# Standing_Desk_Controller_Schematic_v7_v9.net
KiCad netlist of a schematic drawn in EAGLE
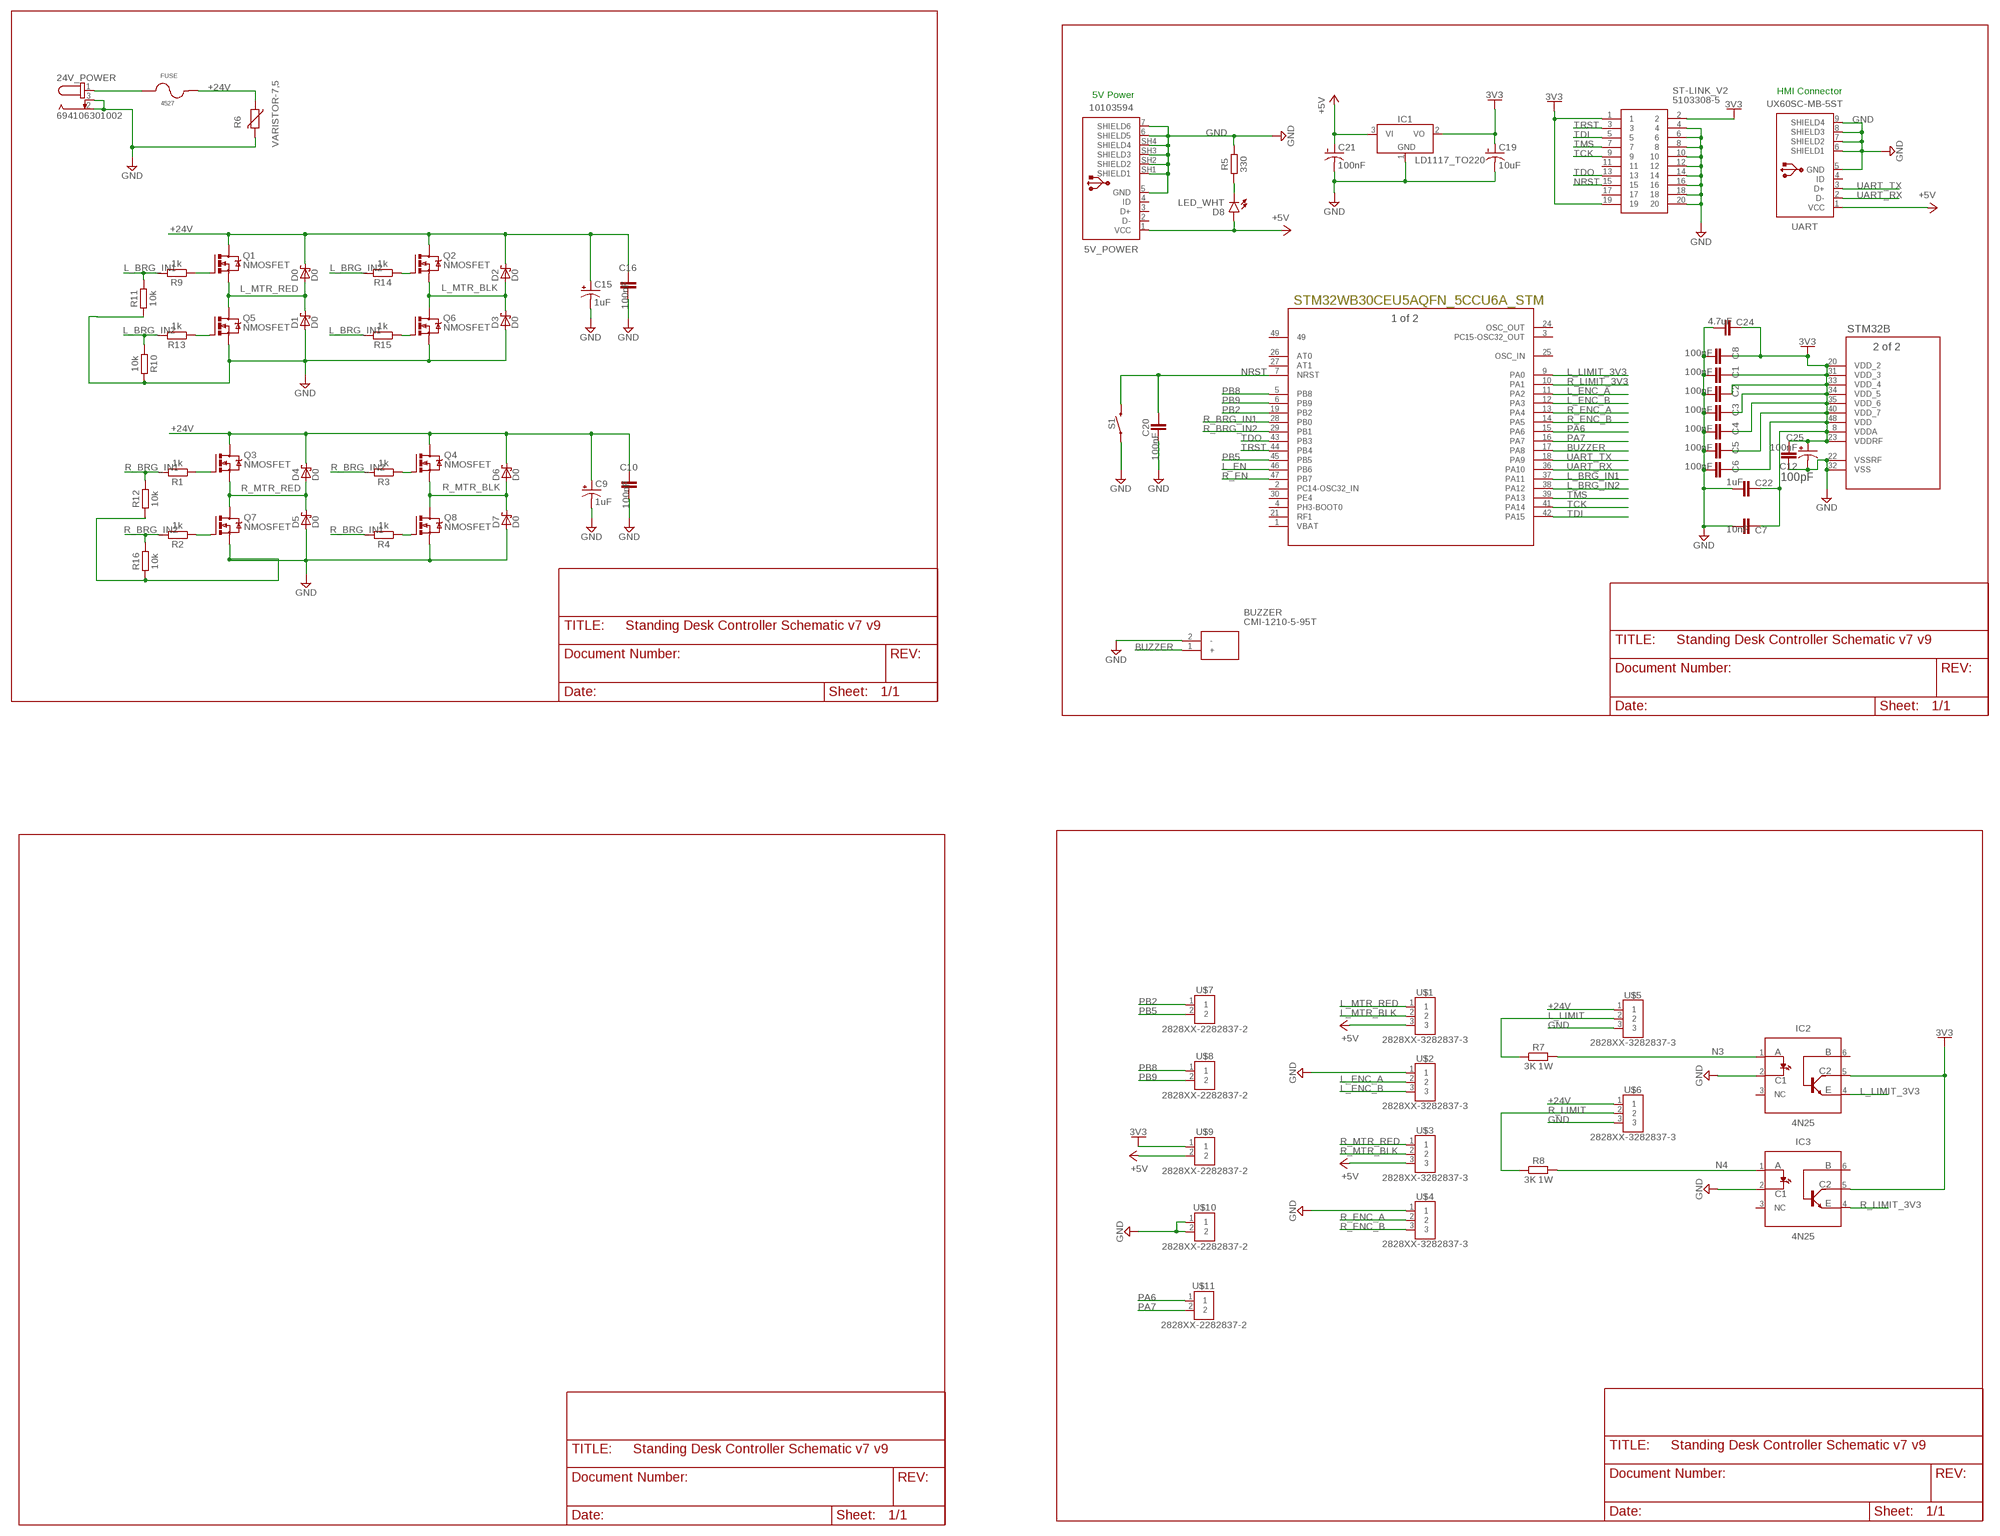
[diagram p0: schematic, sheet 1]

(export (version "E")
  (design (tool "Eeschema 10.0.6"))
  (components
    (comp (ref "5V_POWER")
      (value "10103594")
      (footprint "eagle-import:10103594")
      (fields (field (name "MANUFACTURER") "Amphenol ICC (FCI)") (field (name "MPN") "10103594-0001LF"))
      (libsource (lib "eagle-import") (part "10103594"))
    )
    (comp (ref "24V_POWER")
      (value "694106301002")
      (footprint "eagle-import:694106301002")
      (fields
        (field (name "DIGIKEY_PART_NUMBER") "732-5930-ND")
        (field (name "MANUFACTURER") "Wurth Electronics Inc.")
        (field (name "CREATED_BY") "PCBLayout.com")
      )
      (libsource (lib "eagle-import") (part "694106301002"))
    )
    (comp (ref "BUZZER")
      (value "CMI-1210-5-95T")
      (footprint "eagle-import:CMI1210595T")
      (fields (field (name "MOUSER_PART_NUMBER") "179-CMI-1210-5-95T"))
      (libsource (lib "eagle-import") (part "CMI-1210-5-95T"))
    )
    (comp (ref "C1")
      (value "100nF")
      (footprint "eagle-import:CAPC3216X135")
      (libsource (lib "eagle-import") (part "Capacitor_Bottom_Side_vf.a7xvLcyfRC6FgNyyCREhQg_CCHIP-1206(3216-METRIC)_"))
    )
    (comp (ref "C2")
      (value "100nF")
      (footprint "eagle-import:CAPC3216X135")
      (libsource (lib "eagle-import") (part "Capacitor_Bottom_Side_vf.a7xvLcyfRC6FgNyyCREhQg_CCHIP-1206(3216-METRIC)_"))
    )
    (comp (ref "C3")
      (value "100nF")
      (footprint "eagle-import:CAPC3216X135")
      (libsource (lib "eagle-import") (part "Capacitor_Bottom_Side_vf.a7xvLcyfRC6FgNyyCREhQg_CCHIP-1206(3216-METRIC)_"))
    )
    (comp (ref "C4")
      (value "100nF")
      (footprint "eagle-import:CAPC3216X135")
      (libsource (lib "eagle-import") (part "Capacitor_Bottom_Side_vf.a7xvLcyfRC6FgNyyCREhQg_CCHIP-1206(3216-METRIC)_"))
    )
    (comp (ref "C5")
      (value "100nF")
      (footprint "eagle-import:CAPC3216X135")
      (libsource (lib "eagle-import") (part "Capacitor_Bottom_Side_vf.a7xvLcyfRC6FgNyyCREhQg_CCHIP-1206(3216-METRIC)_"))
    )
    (comp (ref "C6")
      (value "100nF")
      (footprint "eagle-import:CAPC3216X135")
      (libsource (lib "eagle-import") (part "Capacitor_Bottom_Side_vf.a7xvLcyfRC6FgNyyCREhQg_CCHIP-1206(3216-METRIC)_"))
    )
    (comp (ref "C7")
      (value "10nF")
      (footprint "eagle-import:CAPRD550W60D1025H1250B")
      (libsource (lib "eagle-import") (part "CRADIAL-12.5MM-DIA_"))
    )
    (comp (ref "C8")
      (value "100nF")
      (footprint "eagle-import:CAPC3216X135")
      (libsource (lib "eagle-import") (part "Capacitor_Bottom_Side_vf.a7xvLcyfRC6FgNyyCREhQg_CCHIP-1206(3216-METRIC)_"))
    )
    (comp (ref "C9")
      (value "1uF")
      (footprint "eagle-import:E2,5-6")
      (libsource (lib "eagle-import") (part "CPOL-USE2.5-6"))
    )
    (comp (ref "C10")
      (value "100nF")
      (footprint "eagle-import:CAPC3216X135")
      (libsource (lib "eagle-import") (part "Capacitor_16290819_CCHIP-1206(3216-METRIC)_"))
    )
    (comp (ref "C12")
      (value "100nF")
      (footprint "eagle-import:CAPC3216X135")
      (libsource (lib "eagle-import") (part "Capacitor_Bottom_Side_vf.a7xvLcyfRC6FgNyyCREhQg_CCHIP-1206(3216-METRIC)_"))
    )
    (comp (ref "C15")
      (value "1uF")
      (footprint "eagle-import:E2,5-6")
      (libsource (lib "eagle-import") (part "CPOL-USE2.5-6"))
    )
    (comp (ref "C16")
      (value "100nF")
      (footprint "eagle-import:CAPC3216X135")
      (libsource (lib "eagle-import") (part "Capacitor_16290819_CCHIP-1206(3216-METRIC)_"))
    )
    (comp (ref "C19")
      (value "10uF")
      (footprint "eagle-import:E2,5-6")
      (libsource (lib "eagle-import") (part "CPOL-USE2.5-6"))
    )
    (comp (ref "C20")
      (value "100nF")
      (footprint "eagle-import:CAPC3216X135")
      (libsource (lib "eagle-import") (part "Capacitor_16290819_CCHIP-1206(3216-METRIC)_"))
    )
    (comp (ref "C21")
      (value "100nF")
      (footprint "eagle-import:E2,5-6")
      (libsource (lib "eagle-import") (part "CPOL-USE2.5-6"))
    )
    (comp (ref "C22")
      (value "1uF")
      (footprint "eagle-import:CAPRD550W60D1025H1250B")
      (libsource (lib "eagle-import") (part "CRADIAL-12.5MM-DIA_"))
    )
    (comp (ref "C24")
      (value "4.7uF")
      (footprint "eagle-import:CAPRD550W60D1025H1250B")
      (libsource (lib "eagle-import") (part "CRADIAL-12.5MM-DIA_"))
    )
    (comp (ref "C25")
      (value "100pF")
      (footprint "eagle-import:E2,5-6")
      (libsource (lib "eagle-import") (part "CPOL-USE2.5-6"))
    )
    (comp (ref "D0")
      (value "D0")
      (footprint "eagle-import:SOD106A-W")
      (libsource (lib "eagle-import") (part "SS14CT-ND"))
    )
    (comp (ref "D1")
      (value "D0")
      (footprint "eagle-import:SOD106A-W")
      (libsource (lib "eagle-import") (part "SS14CT-ND"))
    )
    (comp (ref "D2")
      (value "D0")
      (footprint "eagle-import:SOD106A-W")
      (libsource (lib "eagle-import") (part "SS14CT-ND"))
    )
    (comp (ref "D3")
      (value "D0")
      (footprint "eagle-import:SOD106A-W")
      (libsource (lib "eagle-import") (part "SS14CT-ND"))
    )
    (comp (ref "D4")
      (value "D0")
      (footprint "eagle-import:SOD106A-W")
      (libsource (lib "eagle-import") (part "SS14CT-ND"))
    )
    (comp (ref "D5")
      (value "D0")
      (footprint "eagle-import:SOD106A-W")
      (libsource (lib "eagle-import") (part "SS14CT-ND"))
    )
    (comp (ref "D6")
      (value "D0")
      (footprint "eagle-import:SOD106A-W")
      (libsource (lib "eagle-import") (part "SS14CT-ND"))
    )
    (comp (ref "D7")
      (value "D0")
      (footprint "eagle-import:SOD106A-W")
      (libsource (lib "eagle-import") (part "SS14CT-ND"))
    )
    (comp (ref "D8")
      (value "LED_WHT")
      (footprint "eagle-import:LEDC3216X75N_FLAT-B")
      (libsource (lib "eagle-import") (part "CHIP-FLAT-B_1206"))
    )
    (comp (ref "FUSE")
      (value "4527")
      (footprint "eagle-import:4527")
      (fields
        (field (name "MANUFACTURER") "Keystone Electronics")
        (field (name "CREATED_BY") "PCBLayout.com")
      )
      (libsource (lib "eagle-import") (part "4527"))
    )
    (comp (ref "IC1")
      (value "LD1117_TO220")
      (footprint "eagle-import:TO220V")
      (fields (field (name "MANUFACTURER") "STMicroelectronics") (field (name "MPN") "Generic"))
      (libsource (lib "eagle-import") (part "LD1117_TO220"))
    )
    (comp (ref "IC2")
      (value "4N25")
      (footprint "eagle-import:DIP762W60P254L712H480Q6B")
      (fields (field (name "MANUFACTURER") "Vishay"))
      (libsource (lib "eagle-import") (part "4N25"))
    )
    (comp (ref "IC3")
      (value "4N25")
      (footprint "eagle-import:DIP762W60P254L712H480Q6B")
      (fields (field (name "MANUFACTURER") "Vishay"))
      (libsource (lib "eagle-import") (part "4N25"))
    )
    (comp (ref "Q1")
      (value "NMOSFET")
      (footprint "eagle-import:TO220BV")
      (libsource (lib "eagle-import") (part "NMOSFETTO220_"))
    )
    (comp (ref "Q2")
      (value "NMOSFET")
      (footprint "eagle-import:TO220BV")
      (libsource (lib "eagle-import") (part "NMOSFETTO220_"))
    )
    (comp (ref "Q3")
      (value "NMOSFET")
      (footprint "eagle-import:TO220BV")
      (libsource (lib "eagle-import") (part "NMOSFETTO220_"))
    )
    (comp (ref "Q4")
      (value "NMOSFET")
      (footprint "eagle-import:TO220BV")
      (libsource (lib "eagle-import") (part "NMOSFETTO220_"))
    )
    (comp (ref "Q5")
      (value "NMOSFET")
      (footprint "eagle-import:TO220BV")
      (libsource (lib "eagle-import") (part "NMOSFETTO220_"))
    )
    (comp (ref "Q6")
      (value "NMOSFET")
      (footprint "eagle-import:TO220BV")
      (libsource (lib "eagle-import") (part "NMOSFETTO220_"))
    )
    (comp (ref "Q7")
      (value "NMOSFET")
      (footprint "eagle-import:TO220BV")
      (libsource (lib "eagle-import") (part "NMOSFETTO220_"))
    )
    (comp (ref "Q8")
      (value "NMOSFET")
      (footprint "eagle-import:TO220BV")
      (libsource (lib "eagle-import") (part "NMOSFETTO220_"))
    )
    (comp (ref "R1")
      (value "1k")
      (footprint "eagle-import:RESC3216X70")
      (libsource (lib "eagle-import") (part "RCHIP-1206(3216-METRIC)_"))
    )
    (comp (ref "R2")
      (value "1k")
      (footprint "eagle-import:RESC3216X70")
      (libsource (lib "eagle-import") (part "RCHIP-1206(3216-METRIC)_"))
    )
    (comp (ref "R3")
      (value "1k")
      (footprint "eagle-import:RESC3216X70")
      (libsource (lib "eagle-import") (part "RCHIP-1206(3216-METRIC)_"))
    )
    (comp (ref "R4")
      (value "1k")
      (footprint "eagle-import:RESC3216X70")
      (libsource (lib "eagle-import") (part "RCHIP-1206(3216-METRIC)_"))
    )
    (comp (ref "R5")
      (value "330")
      (footprint "eagle-import:RESC3216X70")
      (libsource (lib "eagle-import") (part "RCHIP-1206(3216-METRIC)_"))
    )
    (comp (ref "R6")
      (value "VARISTOR-7,5")
      (footprint "eagle-import:R-7,5")
      (libsource (lib "eagle-import") (part "VARISTOR-7,5"))
    )
    (comp (ref "R7")
      (value "3K 1W")
      (footprint "eagle-import:RESAD724W46L381D178B")
      (libsource (lib "eagle-import") (part "RAXIAL-7.2MM-PITCH_"))
    )
    (comp (ref "R8")
      (value "3K 1W")
      (footprint "eagle-import:RESAD724W46L381D178B")
      (libsource (lib "eagle-import") (part "RAXIAL-7.2MM-PITCH_"))
    )
    (comp (ref "R9")
      (value "1k")
      (footprint "eagle-import:RESC3216X70")
      (libsource (lib "eagle-import") (part "RCHIP-1206(3216-METRIC)_"))
    )
    (comp (ref "R10")
      (value "10k")
      (footprint "eagle-import:RESC3216X70")
      (libsource (lib "eagle-import") (part "RCHIP-1206(3216-METRIC)_"))
    )
    (comp (ref "R11")
      (value "10k")
      (footprint "eagle-import:RESC3216X70")
      (libsource (lib "eagle-import") (part "RCHIP-1206(3216-METRIC)_"))
    )
    (comp (ref "R12")
      (value "10k")
      (footprint "eagle-import:RESC3216X70")
      (libsource (lib "eagle-import") (part "RCHIP-1206(3216-METRIC)_"))
    )
    (comp (ref "R13")
      (value "1k")
      (footprint "eagle-import:RESC3216X70")
      (libsource (lib "eagle-import") (part "RCHIP-1206(3216-METRIC)_"))
    )
    (comp (ref "R14")
      (value "1k")
      (footprint "eagle-import:RESC3216X70")
      (libsource (lib "eagle-import") (part "RCHIP-1206(3216-METRIC)_"))
    )
    (comp (ref "R15")
      (value "1k")
      (footprint "eagle-import:RESC3216X70")
      (libsource (lib "eagle-import") (part "RCHIP-1206(3216-METRIC)_"))
    )
    (comp (ref "R16")
      (value "10k")
      (footprint "eagle-import:RESC3216X70")
      (libsource (lib "eagle-import") (part "RCHIP-1206(3216-METRIC)_"))
    )
    (comp (ref "S1")
      (value "MOMENTARY-SWITCH-SPST-PTH-6.0MM")
      (footprint "eagle-import:TACTILE_SWITCH_PTH_6.0MM")
      (libsource (lib "eagle-import") (part "MOMENTARY-SWITCH-SPST-PTH-6.0MM"))
    )
    (comp (ref "ST-LINK_V2")
      (value "5103308-5")
      (footprint "eagle-import:SHDR20W66P254_2X10_3289X914X98")
      (fields (field (name "MOUSER_PART_NUMBER") "571-5103308-5"))
      (libsource (lib "eagle-import") (part "5103308-5"))
    )
    (comp (ref "STM32")
      (value "STM32WB30CEU5AQFN_5CCU6A_STM")
      (footprint "eagle-import:QFN_5CCU6A_STM")
      (fields
        (field (name "MANUFACTURER_PART_NUMBER") "STM32WB30CEU5A")
        (field (name "COPYRIGHT") "Copyright (C) 2022 Ultra Librarian. All rights reserved.")
      )
      (libsource (lib "eagle-import") (part "STM32WB30CEU5AQFN_5CCU6A_STM"))
    )
    (comp (ref "U$1")
      (value "2828XX-3282837-3")
      (footprint "eagle-import:TERMBLK_508-3N")
      (fields (field (name "MANUFACTURER") "TE Connectivity") (field (name "MPN") "282837-3"))
      (libsource (lib "eagle-import") (part "2828XX-3282837-3"))
    )
    (comp (ref "U$2")
      (value "2828XX-3282837-3")
      (footprint "eagle-import:TERMBLK_508-3N")
      (fields (field (name "MANUFACTURER") "TE Connectivity") (field (name "MPN") "282837-3"))
      (libsource (lib "eagle-import") (part "2828XX-3282837-3"))
    )
    (comp (ref "U$3")
      (value "2828XX-3282837-3")
      (footprint "eagle-import:TERMBLK_508-3N")
      (fields (field (name "MANUFACTURER") "TE Connectivity") (field (name "MPN") "282837-3"))
      (libsource (lib "eagle-import") (part "2828XX-3282837-3"))
    )
    (comp (ref "U$4")
      (value "2828XX-3282837-3")
      (footprint "eagle-import:TERMBLK_508-3N")
      (fields (field (name "MANUFACTURER") "TE Connectivity") (field (name "MPN") "282837-3"))
      (libsource (lib "eagle-import") (part "2828XX-3282837-3"))
    )
    (comp (ref "U$5")
      (value "2828XX-3282837-3")
      (footprint "eagle-import:TERMBLK_508-3N")
      (fields (field (name "MANUFACTURER") "TE Connectivity") (field (name "MPN") "282837-3"))
      (libsource (lib "eagle-import") (part "2828XX-3282837-3"))
    )
    (comp (ref "U$6")
      (value "2828XX-3282837-3")
      (footprint "eagle-import:TERMBLK_508-3N")
      (fields (field (name "MANUFACTURER") "TE Connectivity") (field (name "MPN") "282837-3"))
      (libsource (lib "eagle-import") (part "2828XX-3282837-3"))
    )
    (comp (ref "U$7")
      (value "2828XX-2282837-2")
      (footprint "eagle-import:TERMBLK_508-2N")
      (fields (field (name "MANUFACTURER") "TE Connectivity") (field (name "MPN") "282837-2"))
      (libsource (lib "eagle-import") (part "2828XX-2282837-2"))
    )
    (comp (ref "U$8")
      (value "2828XX-2282837-2")
      (footprint "eagle-import:TERMBLK_508-2N")
      (fields (field (name "MANUFACTURER") "TE Connectivity") (field (name "MPN") "282837-2"))
      (libsource (lib "eagle-import") (part "2828XX-2282837-2"))
    )
    (comp (ref "U$9")
      (value "2828XX-2282837-2")
      (footprint "eagle-import:TERMBLK_508-2N")
      (fields (field (name "MANUFACTURER") "TE Connectivity") (field (name "MPN") "282837-2"))
      (libsource (lib "eagle-import") (part "2828XX-2282837-2"))
    )
    (comp (ref "U$10")
      (value "2828XX-2282837-2")
      (footprint "eagle-import:TERMBLK_508-2N")
      (fields (field (name "MANUFACTURER") "TE Connectivity") (field (name "MPN") "282837-2"))
      (libsource (lib "eagle-import") (part "2828XX-2282837-2"))
    )
    (comp (ref "U$11")
      (value "2828XX-2282837-2")
      (footprint "eagle-import:TERMBLK_508-2N")
      (fields (field (name "MANUFACTURER") "TE Connectivity") (field (name "MPN") "282837-2"))
      (libsource (lib "eagle-import") (part "2828XX-2282837-2"))
    )
    (comp (ref "UART")
      (value "UX60SC-MB-5ST")
      (footprint "eagle-import:UX60SC-MB-5ST")
      (fields
        (field (name "MANUFACTURER") "Hirose Electric Co. Ltd")
        (field (name "MPN") "UX60SC-MB-5ST(80)")
      )
      (libsource (lib "eagle-import") (part "UX60SC-MB-5ST"))
    )
  )
  (nets
    (net (code "1") (name "+5V") (class "Default")
      (node (ref "5V_POWER") (pin "1") (pinfunction "VCC_1") (pintype "power_in"))
      (node (ref "C21") (pin "+") (pinfunction "+_+") (pintype "passive"))
      (node (ref "D8") (pin "A") (pinfunction "A_A") (pintype "passive"))
      (node (ref "IC1") (pin "3") (pinfunction "VI_3") (pintype "input"))
      (node (ref "U$1") (pin "3") (pinfunction "3_3") (pintype "bidirectional"))
      (node (ref "U$3") (pin "3") (pinfunction "3_3") (pintype "bidirectional"))
      (node (ref "U$9") (pin "2") (pinfunction "2_2") (pintype "bidirectional"))
      (node (ref "UART") (pin "1") (pinfunction "VCC_1") (pintype "power_in"))
    )
    (net (code "2") (name "/+24V") (class "Default")
      (node (ref "C10") (pin "1") (pinfunction "1_1") (pintype "passive"))
      (node (ref "C15") (pin "+") (pinfunction "+_+") (pintype "passive"))
      (node (ref "C16") (pin "1") (pinfunction "1_1") (pintype "passive"))
      (node (ref "C9") (pin "+") (pinfunction "+_+") (pintype "passive"))
      (node (ref "D0") (pin "C") (pinfunction "C_C") (pintype "passive"))
      (node (ref "D2") (pin "C") (pinfunction "C_C") (pintype "passive"))
      (node (ref "D4") (pin "C") (pinfunction "C_C") (pintype "passive"))
      (node (ref "D6") (pin "C") (pinfunction "C_C") (pintype "passive"))
      (node (ref "FUSE") (pin "2") (pinfunction "2_2") (pintype "passive"))
      (node (ref "Q1") (pin "D") (pinfunction "D_D") (pintype "passive"))
      (node (ref "Q2") (pin "D") (pinfunction "D_D") (pintype "passive"))
      (node (ref "Q3") (pin "D") (pinfunction "D_D") (pintype "passive"))
      (node (ref "Q4") (pin "D") (pinfunction "D_D") (pintype "passive"))
      (node (ref "R6") (pin "1") (pinfunction "1_1") (pintype "passive"))
      (node (ref "U$5") (pin "1") (pinfunction "1_1") (pintype "bidirectional"))
      (node (ref "U$6") (pin "1") (pinfunction "1_1") (pintype "bidirectional"))
    )
    (net (code "3") (name "/BUZZER") (class "Default")
      (node (ref "BUZZER") (pin "1") (pinfunction "+_1") (pintype "bidirectional"))
      (node (ref "STM32") (pin "17") (pinfunction "PA8_17") (pintype "bidirectional"))
    )
    (net (code "4") (name "/L_BRG_IN1") (class "Default")
      (node (ref "R11") (pin "2") (pinfunction "2_2") (pintype "passive"))
      (node (ref "R15") (pin "2") (pinfunction "2_2") (pintype "passive"))
      (node (ref "R9") (pin "2") (pinfunction "2_2") (pintype "passive"))
      (node (ref "STM32") (pin "37") (pinfunction "PA11_37") (pintype "bidirectional"))
    )
    (net (code "5") (name "/L_BRG_IN2") (class "Default")
      (node (ref "R10") (pin "1") (pinfunction "1_1") (pintype "passive"))
      (node (ref "R13") (pin "2") (pinfunction "2_2") (pintype "passive"))
      (node (ref "R14") (pin "2") (pinfunction "2_2") (pintype "passive"))
      (node (ref "STM32") (pin "38") (pinfunction "PA12_38") (pintype "bidirectional"))
    )
    (net (code "6") (name "/L_EN") (class "Default")
      (node (ref "STM32") (pin "46") (pinfunction "PB6_46") (pintype "bidirectional"))
    )
    (net (code "7") (name "/L_ENC_A") (class "Default")
      (node (ref "STM32") (pin "11") (pinfunction "PA2_11") (pintype "bidirectional"))
      (node (ref "U$2") (pin "2") (pinfunction "2_2") (pintype "bidirectional"))
    )
    (net (code "8") (name "/L_ENC_B") (class "Default")
      (node (ref "STM32") (pin "12") (pinfunction "PA3_12") (pintype "bidirectional"))
      (node (ref "U$2") (pin "3") (pinfunction "3_3") (pintype "bidirectional"))
    )
    (net (code "9") (name "/L_LIMIT") (class "Default")
      (node (ref "R7") (pin "1") (pinfunction "1_1") (pintype "passive"))
      (node (ref "U$5") (pin "2") (pinfunction "2_2") (pintype "bidirectional"))
    )
    (net (code "10") (name "/L_LIMIT_3V3") (class "Default")
      (node (ref "IC2") (pin "4") (pinfunction "E_4") (pintype "passive"))
      (node (ref "STM32") (pin "9") (pinfunction "PA0_9") (pintype "bidirectional"))
    )
    (net (code "11") (name "/L_MTR_BLK") (class "Default")
      (node (ref "D2") (pin "A") (pinfunction "A_A") (pintype "passive"))
      (node (ref "D3") (pin "C") (pinfunction "C_C") (pintype "passive"))
      (node (ref "Q2") (pin "S") (pinfunction "S_S") (pintype "passive"))
      (node (ref "Q6") (pin "D") (pinfunction "D_D") (pintype "passive"))
      (node (ref "U$1") (pin "2") (pinfunction "2_2") (pintype "bidirectional"))
    )
    (net (code "12") (name "/L_MTR_RED") (class "Default")
      (node (ref "D0") (pin "A") (pinfunction "A_A") (pintype "passive"))
      (node (ref "D1") (pin "C") (pinfunction "C_C") (pintype "passive"))
      (node (ref "Q1") (pin "S") (pinfunction "S_S") (pintype "passive"))
      (node (ref "Q5") (pin "D") (pinfunction "D_D") (pintype "passive"))
      (node (ref "U$1") (pin "1") (pinfunction "1_1") (pintype "bidirectional"))
    )
    (net (code "13") (name "/N3") (class "Default")
      (node (ref "IC2") (pin "1") (pinfunction "A_1") (pintype "passive"))
      (node (ref "R7") (pin "2") (pinfunction "2_2") (pintype "passive"))
    )
    (net (code "14") (name "/N4") (class "Default")
      (node (ref "IC3") (pin "1") (pinfunction "A_1") (pintype "passive"))
      (node (ref "R8") (pin "2") (pinfunction "2_2") (pintype "passive"))
    )
    (net (code "15") (name "/NRST") (class "Default")
      (node (ref "C20") (pin "1") (pinfunction "1_1") (pintype "passive"))
      (node (ref "S1") (pin "3") (pinfunction "2_3") (pintype "passive"))
      (node (ref "ST-LINK_V2") (pin "15") (pinfunction "15_15") (pintype "bidirectional"))
      (node (ref "STM32") (pin "7") (pinfunction "NRST_7") (pintype "passive"))
    )
    (net (code "16") (name "/PA6") (class "Default")
      (node (ref "STM32") (pin "15") (pinfunction "PA6_15") (pintype "bidirectional"))
      (node (ref "U$11") (pin "1") (pinfunction "1_1") (pintype "bidirectional"))
    )
    (net (code "17") (name "/PA7") (class "Default")
      (node (ref "STM32") (pin "16") (pinfunction "PA7_16") (pintype "bidirectional"))
      (node (ref "U$11") (pin "2") (pinfunction "2_2") (pintype "bidirectional"))
    )
    (net (code "18") (name "/PB2") (class "Default")
      (node (ref "STM32") (pin "19") (pinfunction "PB2_19") (pintype "bidirectional"))
      (node (ref "U$7") (pin "1") (pinfunction "1_1") (pintype "bidirectional"))
    )
    (net (code "19") (name "/PB5") (class "Default")
      (node (ref "STM32") (pin "45") (pinfunction "PB5_45") (pintype "bidirectional"))
      (node (ref "U$7") (pin "2") (pinfunction "2_2") (pintype "bidirectional"))
    )
    (net (code "20") (name "/PB8") (class "Default")
      (node (ref "STM32") (pin "5") (pinfunction "PB8_5") (pintype "bidirectional"))
      (node (ref "U$8") (pin "1") (pinfunction "1_1") (pintype "bidirectional"))
    )
    (net (code "21") (name "/PB9") (class "Default")
      (node (ref "STM32") (pin "6") (pinfunction "PB9_6") (pintype "bidirectional"))
      (node (ref "U$8") (pin "2") (pinfunction "2_2") (pintype "bidirectional"))
    )
    (net (code "22") (name "/R_BRG_IN1") (class "Default")
      (node (ref "R1") (pin "2") (pinfunction "2_2") (pintype "passive"))
      (node (ref "R12") (pin "2") (pinfunction "2_2") (pintype "passive"))
      (node (ref "R4") (pin "2") (pinfunction "2_2") (pintype "passive"))
      (node (ref "STM32") (pin "28") (pinfunction "PB0_28") (pintype "bidirectional"))
    )
    (net (code "23") (name "/R_BRG_IN2") (class "Default")
      (node (ref "R16") (pin "2") (pinfunction "2_2") (pintype "passive"))
      (node (ref "R2") (pin "2") (pinfunction "2_2") (pintype "passive"))
      (node (ref "R3") (pin "2") (pinfunction "2_2") (pintype "passive"))
      (node (ref "STM32") (pin "29") (pinfunction "PB1_29") (pintype "bidirectional"))
    )
    (net (code "24") (name "/R_EN") (class "Default")
      (node (ref "STM32") (pin "47") (pinfunction "PB7_47") (pintype "bidirectional"))
    )
    (net (code "25") (name "/R_ENC_A") (class "Default")
      (node (ref "STM32") (pin "13") (pinfunction "PA4_13") (pintype "bidirectional"))
      (node (ref "U$4") (pin "2") (pinfunction "2_2") (pintype "bidirectional"))
    )
    (net (code "26") (name "/R_ENC_B") (class "Default")
      (node (ref "STM32") (pin "14") (pinfunction "PA5_14") (pintype "bidirectional"))
      (node (ref "U$4") (pin "3") (pinfunction "3_3") (pintype "bidirectional"))
    )
    (net (code "27") (name "/R_LIMIT") (class "Default")
      (node (ref "R8") (pin "1") (pinfunction "1_1") (pintype "passive"))
      (node (ref "U$6") (pin "2") (pinfunction "2_2") (pintype "bidirectional"))
    )
    (net (code "28") (name "/R_LIMIT_3V3") (class "Default")
      (node (ref "IC3") (pin "4") (pinfunction "E_4") (pintype "passive"))
      (node (ref "STM32") (pin "10") (pinfunction "PA1_10") (pintype "bidirectional"))
    )
    (net (code "29") (name "/R_MTR_BLK") (class "Default")
      (node (ref "D6") (pin "A") (pinfunction "A_A") (pintype "passive"))
      (node (ref "D7") (pin "C") (pinfunction "C_C") (pintype "passive"))
      (node (ref "Q4") (pin "S") (pinfunction "S_S") (pintype "passive"))
      (node (ref "Q8") (pin "D") (pinfunction "D_D") (pintype "passive"))
      (node (ref "U$3") (pin "2") (pinfunction "2_2") (pintype "bidirectional"))
    )
    (net (code "30") (name "/R_MTR_RED") (class "Default")
      (node (ref "D4") (pin "A") (pinfunction "A_A") (pintype "passive"))
      (node (ref "D5") (pin "C") (pinfunction "C_C") (pintype "passive"))
      (node (ref "Q3") (pin "S") (pinfunction "S_S") (pintype "passive"))
      (node (ref "Q7") (pin "D") (pinfunction "D_D") (pintype "passive"))
      (node (ref "U$3") (pin "1") (pinfunction "1_1") (pintype "bidirectional"))
    )
    (net (code "31") (name "/TCK") (class "Default")
      (node (ref "ST-LINK_V2") (pin "9") (pinfunction "9_9") (pintype "bidirectional"))
      (node (ref "STM32") (pin "41") (pinfunction "PA14_41") (pintype "bidirectional"))
    )
    (net (code "32") (name "/TDI") (class "Default")
      (node (ref "ST-LINK_V2") (pin "5") (pinfunction "5_5") (pintype "bidirectional"))
      (node (ref "STM32") (pin "42") (pinfunction "PA15_42") (pintype "bidirectional"))
    )
    (net (code "33") (name "/TDO") (class "Default")
      (node (ref "ST-LINK_V2") (pin "13") (pinfunction "13_13") (pintype "bidirectional"))
      (node (ref "STM32") (pin "43") (pinfunction "PB3_43") (pintype "bidirectional"))
    )
    (net (code "34") (name "/TMS") (class "Default")
      (node (ref "ST-LINK_V2") (pin "7") (pinfunction "7_7") (pintype "bidirectional"))
      (node (ref "STM32") (pin "39") (pinfunction "PA13_39") (pintype "bidirectional"))
    )
    (net (code "35") (name "/TRST") (class "Default")
      (node (ref "ST-LINK_V2") (pin "3") (pinfunction "3_3") (pintype "bidirectional"))
      (node (ref "STM32") (pin "44") (pinfunction "PB4_44") (pintype "bidirectional"))
    )
    (net (code "36") (name "/UART_RX") (class "Default")
      (node (ref "STM32") (pin "36") (pinfunction "PA10_36") (pintype "bidirectional"))
      (node (ref "UART") (pin "2") (pinfunction "D-_2") (pintype "bidirectional"))
    )
    (net (code "37") (name "/UART_TX") (class "Default")
      (node (ref "STM32") (pin "18") (pinfunction "PA9_18") (pintype "bidirectional"))
      (node (ref "UART") (pin "3") (pinfunction "D+_3") (pintype "bidirectional"))
    )
    (net (code "38") (name "3V3") (class "Default")
      (node (ref "C1") (pin "1") (pinfunction "1_1") (pintype "passive"))
      (node (ref "C12") (pin "1") (pinfunction "1_1") (pintype "passive"))
      (node (ref "C19") (pin "+") (pinfunction "+_+") (pintype "passive"))
      (node (ref "C2") (pin "1") (pinfunction "1_1") (pintype "passive"))
      (node (ref "C22") (pin "1") (pinfunction "1_1") (pintype "passive"))
      (node (ref "C24") (pin "1") (pinfunction "1_1") (pintype "passive"))
      (node (ref "C25") (pin "+") (pinfunction "+_+") (pintype "passive"))
      (node (ref "C3") (pin "1") (pinfunction "1_1") (pintype "passive"))
      (node (ref "C4") (pin "1") (pinfunction "1_1") (pintype "passive"))
      (node (ref "C5") (pin "1") (pinfunction "1_1") (pintype "passive"))
      (node (ref "C6") (pin "1") (pinfunction "1_1") (pintype "passive"))
      (node (ref "C7") (pin "1") (pinfunction "1_1") (pintype "passive"))
      (node (ref "C8") (pin "1") (pinfunction "1_1") (pintype "passive"))
      (node (ref "IC1") (pin "2") (pinfunction "VO_2") (pintype "output"))
      (node (ref "IC2") (pin "5") (pinfunction "C2_5") (pintype "passive"))
      (node (ref "IC3") (pin "5") (pinfunction "C2_5") (pintype "passive"))
      (node (ref "ST-LINK_V2") (pin "1") (pinfunction "1_1") (pintype "bidirectional"))
      (node (ref "ST-LINK_V2") (pin "19") (pinfunction "19_19") (pintype "bidirectional"))
      (node (ref "ST-LINK_V2") (pin "2") (pinfunction "2_2") (pintype "bidirectional"))
      (node (ref "STM32") (pin "20") (pinfunction "VDD_2_20") (pintype "power_in"))
      (node (ref "STM32") (pin "23") (pinfunction "VDDRF_23") (pintype "power_in"))
      (node (ref "STM32") (pin "31") (pinfunction "VDD_3_31") (pintype "power_in"))
      (node (ref "STM32") (pin "33") (pinfunction "VDD_4_33") (pintype "power_in"))
      (node (ref "STM32") (pin "34") (pinfunction "VDD_5_34") (pintype "power_in"))
      (node (ref "STM32") (pin "35") (pinfunction "VDD_6_35") (pintype "power_in"))
      (node (ref "STM32") (pin "40") (pinfunction "VDD_7_40") (pintype "power_in"))
      (node (ref "STM32") (pin "48") (pinfunction "VDD_48") (pintype "power_in"))
      (node (ref "STM32") (pin "8") (pinfunction "VDDA_8") (pintype "power_in"))
      (node (ref "U$9") (pin "1") (pinfunction "1_1") (pintype "bidirectional"))
    )
    (net (code "39") (name "GND") (class "Default")
      (node (ref "24V_POWER") (pin "2") (pinfunction "2_2") (pintype "passive"))
      (node (ref "24V_POWER") (pin "3") (pinfunction "3_3") (pintype "passive"))
      (node (ref "5V_POWER") (pin "5") (pinfunction "GND_5") (pintype "power_in"))
      (node (ref "5V_POWER") (pin "6") (pinfunction "SHIELD5_6") (pintype "power_in"))
      (node (ref "5V_POWER") (pin "7") (pinfunction "SHIELD6_7") (pintype "power_in"))
      (node (ref "5V_POWER") (pin "SH1") (pinfunction "SHIELD1_SH1") (pintype "power_in"))
      (node (ref "5V_POWER") (pin "SH2") (pinfunction "SHIELD2_SH2") (pintype "power_in"))
      (node (ref "5V_POWER") (pin "SH3") (pinfunction "SHIELD3_SH3") (pintype "power_in"))
      (node (ref "5V_POWER") (pin "SH4") (pinfunction "SHIELD4_SH4") (pintype "power_in"))
      (node (ref "BUZZER") (pin "2") (pinfunction "-_2") (pintype "bidirectional"))
      (node (ref "C1") (pin "2") (pinfunction "2_2") (pintype "passive"))
      (node (ref "C10") (pin "2") (pinfunction "2_2") (pintype "passive"))
      (node (ref "C12") (pin "2") (pinfunction "2_2") (pintype "passive"))
      (node (ref "C15") (pin "-") (pinfunction "-_-") (pintype "passive"))
      (node (ref "C16") (pin "2") (pinfunction "2_2") (pintype "passive"))
      (node (ref "C19") (pin "-") (pinfunction "-_-") (pintype "passive"))
      (node (ref "C2") (pin "2") (pinfunction "2_2") (pintype "passive"))
      (node (ref "C20") (pin "2") (pinfunction "2_2") (pintype "passive"))
      (node (ref "C21") (pin "-") (pinfunction "-_-") (pintype "passive"))
      (node (ref "C22") (pin "2") (pinfunction "2_2") (pintype "passive"))
      (node (ref "C24") (pin "2") (pinfunction "2_2") (pintype "passive"))
      (node (ref "C25") (pin "-") (pinfunction "-_-") (pintype "passive"))
      (node (ref "C3") (pin "2") (pinfunction "2_2") (pintype "passive"))
      (node (ref "C4") (pin "2") (pinfunction "2_2") (pintype "passive"))
      (node (ref "C5") (pin "2") (pinfunction "2_2") (pintype "passive"))
      (node (ref "C6") (pin "2") (pinfunction "2_2") (pintype "passive"))
      (node (ref "C7") (pin "2") (pinfunction "2_2") (pintype "passive"))
      (node (ref "C8") (pin "2") (pinfunction "2_2") (pintype "passive"))
      (node (ref "C9") (pin "-") (pinfunction "-_-") (pintype "passive"))
      (node (ref "D1") (pin "A") (pinfunction "A_A") (pintype "passive"))
      (node (ref "D3") (pin "A") (pinfunction "A_A") (pintype "passive"))
      (node (ref "D5") (pin "A") (pinfunction "A_A") (pintype "passive"))
      (node (ref "D7") (pin "A") (pinfunction "A_A") (pintype "passive"))
      (node (ref "IC1") (pin "1") (pinfunction "GND_1") (pintype "passive"))
      (node (ref "IC2") (pin "2") (pinfunction "C1_2") (pintype "passive"))
      (node (ref "IC3") (pin "2") (pinfunction "C1_2") (pintype "passive"))
      (node (ref "Q5") (pin "S") (pinfunction "S_S") (pintype "passive"))
      (node (ref "Q6") (pin "S") (pinfunction "S_S") (pintype "passive"))
      (node (ref "Q7") (pin "S") (pinfunction "S_S") (pintype "passive"))
      (node (ref "Q8") (pin "S") (pinfunction "S_S") (pintype "passive"))
      (node (ref "R10") (pin "2") (pinfunction "2_2") (pintype "passive"))
      (node (ref "R11") (pin "1") (pinfunction "1_1") (pintype "passive"))
      (node (ref "R12") (pin "1") (pinfunction "1_1") (pintype "passive"))
      (node (ref "R16") (pin "1") (pinfunction "1_1") (pintype "passive"))
      (node (ref "R5") (pin "2") (pinfunction "2_2") (pintype "passive"))
      (node (ref "R6") (pin "2") (pinfunction "2_2") (pintype "passive"))
      (node (ref "S1") (pin "1") (pinfunction "1_1") (pintype "passive"))
      (node (ref "ST-LINK_V2") (pin "10") (pinfunction "10_10") (pintype "bidirectional"))
      (node (ref "ST-LINK_V2") (pin "12") (pinfunction "12_12") (pintype "bidirectional"))
      (node (ref "ST-LINK_V2") (pin "14") (pinfunction "14_14") (pintype "bidirectional"))
      (node (ref "ST-LINK_V2") (pin "16") (pinfunction "16_16") (pintype "bidirectional"))
      (node (ref "ST-LINK_V2") (pin "18") (pinfunction "18_18") (pintype "bidirectional"))
      (node (ref "ST-LINK_V2") (pin "20") (pinfunction "20_20") (pintype "bidirectional"))
      (node (ref "ST-LINK_V2") (pin "4") (pinfunction "4_4") (pintype "bidirectional"))
      (node (ref "ST-LINK_V2") (pin "6") (pinfunction "6_6") (pintype "bidirectional"))
      (node (ref "ST-LINK_V2") (pin "8") (pinfunction "8_8") (pintype "bidirectional"))
      (node (ref "STM32") (pin "22") (pinfunction "VSSRF_22") (pintype "passive"))
      (node (ref "STM32") (pin "32") (pinfunction "VSS_32") (pintype "passive"))
      (node (ref "U$10") (pin "1") (pinfunction "1_1") (pintype "bidirectional"))
      (node (ref "U$10") (pin "2") (pinfunction "2_2") (pintype "bidirectional"))
      (node (ref "U$2") (pin "1") (pinfunction "1_1") (pintype "bidirectional"))
      (node (ref "U$4") (pin "1") (pinfunction "1_1") (pintype "bidirectional"))
      (node (ref "U$5") (pin "3") (pinfunction "3_3") (pintype "bidirectional"))
      (node (ref "U$6") (pin "3") (pinfunction "3_3") (pintype "bidirectional"))
      (node (ref "UART") (pin "5") (pinfunction "GND_5") (pintype "power_in"))
      (node (ref "UART") (pin "6") (pinfunction "SHIELD1_6") (pintype "power_in"))
      (node (ref "UART") (pin "7") (pinfunction "SHIELD2_7") (pintype "power_in"))
      (node (ref "UART") (pin "8") (pinfunction "SHIELD3_8") (pintype "power_in"))
      (node (ref "UART") (pin "9") (pinfunction "SHIELD4_9") (pintype "power_in"))
    )
    (net (code "40") (name "Net-(24V_POWER-Pad1)") (class "Default")
      (node (ref "24V_POWER") (pin "1") (pinfunction "1_1") (pintype "passive"))
      (node (ref "FUSE") (pin "1") (pinfunction "1_1") (pintype "passive"))
    )
    (net (code "41") (name "Net-(D8-PadC)") (class "Default")
      (node (ref "D8") (pin "C") (pinfunction "C_C") (pintype "passive"))
      (node (ref "R5") (pin "1") (pinfunction "1_1") (pintype "passive"))
    )
    (net (code "42") (name "Net-(Q1-PadG)") (class "Default")
      (node (ref "Q1") (pin "G") (pinfunction "G_G") (pintype "passive"))
      (node (ref "R9") (pin "1") (pinfunction "1_1") (pintype "passive"))
    )
    (net (code "43") (name "Net-(Q2-PadG)") (class "Default")
      (node (ref "Q2") (pin "G") (pinfunction "G_G") (pintype "passive"))
      (node (ref "R14") (pin "1") (pinfunction "1_1") (pintype "passive"))
    )
    (net (code "44") (name "Net-(Q3-PadG)") (class "Default")
      (node (ref "Q3") (pin "G") (pinfunction "G_G") (pintype "passive"))
      (node (ref "R1") (pin "1") (pinfunction "1_1") (pintype "passive"))
    )
    (net (code "45") (name "Net-(Q4-PadG)") (class "Default")
      (node (ref "Q4") (pin "G") (pinfunction "G_G") (pintype "passive"))
      (node (ref "R3") (pin "1") (pinfunction "1_1") (pintype "passive"))
    )
    (net (code "46") (name "Net-(Q5-PadG)") (class "Default")
      (node (ref "Q5") (pin "G") (pinfunction "G_G") (pintype "passive"))
      (node (ref "R13") (pin "1") (pinfunction "1_1") (pintype "passive"))
    )
    (net (code "47") (name "Net-(Q6-PadG)") (class "Default")
      (node (ref "Q6") (pin "G") (pinfunction "G_G") (pintype "passive"))
      (node (ref "R15") (pin "1") (pinfunction "1_1") (pintype "passive"))
    )
    (net (code "48") (name "Net-(Q7-PadG)") (class "Default")
      (node (ref "Q7") (pin "G") (pinfunction "G_G") (pintype "passive"))
      (node (ref "R2") (pin "1") (pinfunction "1_1") (pintype "passive"))
    )
    (net (code "49") (name "Net-(Q8-PadG)") (class "Default")
      (node (ref "Q8") (pin "G") (pinfunction "G_G") (pintype "passive"))
      (node (ref "R4") (pin "1") (pinfunction "1_1") (pintype "passive"))
    )
    (net (code "50") (name "unconnected-(5V_POWER-D+-Pad3)") (class "Default")
      (node (ref "5V_POWER") (pin "3") (pinfunction "D+_3") (pintype "bidirectional"))
    )
    (net (code "51") (name "unconnected-(5V_POWER-D--Pad2)") (class "Default")
      (node (ref "5V_POWER") (pin "2") (pinfunction "D-_2") (pintype "bidirectional"))
    )
    (net (code "52") (name "unconnected-(5V_POWER-ID-Pad4)") (class "Default")
      (node (ref "5V_POWER") (pin "4") (pinfunction "ID_4") (pintype "bidirectional"))
    )
    (net (code "53") (name "unconnected-(IC2-B-Pad6)") (class "Default")
      (node (ref "IC2") (pin "6") (pinfunction "B_6") (pintype "passive"))
    )
    (net (code "54") (name "unconnected-(IC2-NC-Pad3)") (class "Default")
      (node (ref "IC2") (pin "3") (pinfunction "NC_3") (pintype "no_connect"))
    )
    (net (code "55") (name "unconnected-(IC3-B-Pad6)") (class "Default")
      (node (ref "IC3") (pin "6") (pinfunction "B_6") (pintype "passive"))
    )
    (net (code "56") (name "unconnected-(IC3-NC-Pad3)") (class "Default")
      (node (ref "IC3") (pin "3") (pinfunction "NC_3") (pintype "no_connect"))
    )
    (net (code "57") (name "unconnected-(ST-LINK_V2-Pad11)") (class "Default")
      (node (ref "ST-LINK_V2") (pin "11") (pinfunction "11_11") (pintype "bidirectional"))
    )
    (net (code "58") (name "unconnected-(ST-LINK_V2-Pad17)") (class "Default")
      (node (ref "ST-LINK_V2") (pin "17") (pinfunction "17_17") (pintype "bidirectional"))
    )
    (net (code "59") (name "unconnected-(STM32-Pad49)") (class "Default")
      (node (ref "STM32") (pin "49") (pinfunction "49_49") (pintype "passive"))
    )
    (net (code "60") (name "unconnected-(STM32A-AT0-Pad26)") (class "Default")
      (node (ref "STM32") (pin "26") (pinfunction "AT0_26") (pintype "bidirectional"))
    )
    (net (code "61") (name "unconnected-(STM32A-AT1-Pad27)") (class "Default")
      (node (ref "STM32") (pin "27") (pinfunction "AT1_27") (pintype "bidirectional"))
    )
    (net (code "62") (name "unconnected-(STM32A-OSC_IN-Pad25)") (class "Default")
      (node (ref "STM32") (pin "25") (pinfunction "OSC_IN_25") (pintype "passive"))
    )
    (net (code "63") (name "unconnected-(STM32A-OSC_OUT-Pad24)") (class "Default")
      (node (ref "STM32") (pin "24") (pinfunction "OSC_OUT_24") (pintype "output"))
    )
    (net (code "64") (name "unconnected-(STM32A-PC14-OSC32_IN-Pad2)") (class "Default")
      (node (ref "STM32") (pin "2") (pinfunction "PC14-OSC32_IN_2") (pintype "bidirectional"))
    )
    (net (code "65") (name "unconnected-(STM32A-PC15-OSC32_OUT-Pad3)") (class "Default")
      (node (ref "STM32") (pin "3") (pinfunction "PC15-OSC32_OUT_3") (pintype "output"))
    )
    (net (code "66") (name "unconnected-(STM32A-PE4-Pad30)") (class "Default")
      (node (ref "STM32") (pin "30") (pinfunction "PE4_30") (pintype "passive"))
    )
    (net (code "67") (name "unconnected-(STM32A-PH3-BOOT0-Pad4)") (class "Default")
      (node (ref "STM32") (pin "4") (pinfunction "PH3-BOOT0_4") (pintype "passive"))
    )
    (net (code "68") (name "unconnected-(STM32A-RF1-Pad21)") (class "Default")
      (node (ref "STM32") (pin "21") (pinfunction "RF1_21") (pintype "passive"))
    )
    (net (code "69") (name "unconnected-(STM32A-VBAT-Pad1)") (class "Default")
      (node (ref "STM32") (pin "1") (pinfunction "VBAT_1") (pintype "passive"))
    )
    (net (code "70") (name "unconnected-(UART-ID-Pad4)") (class "Default")
      (node (ref "UART") (pin "4") (pinfunction "ID_4") (pintype "bidirectional"))
    )
  )
)
